# ethernet.net
KiCad netlist of a schematic drawn in Altium Designer
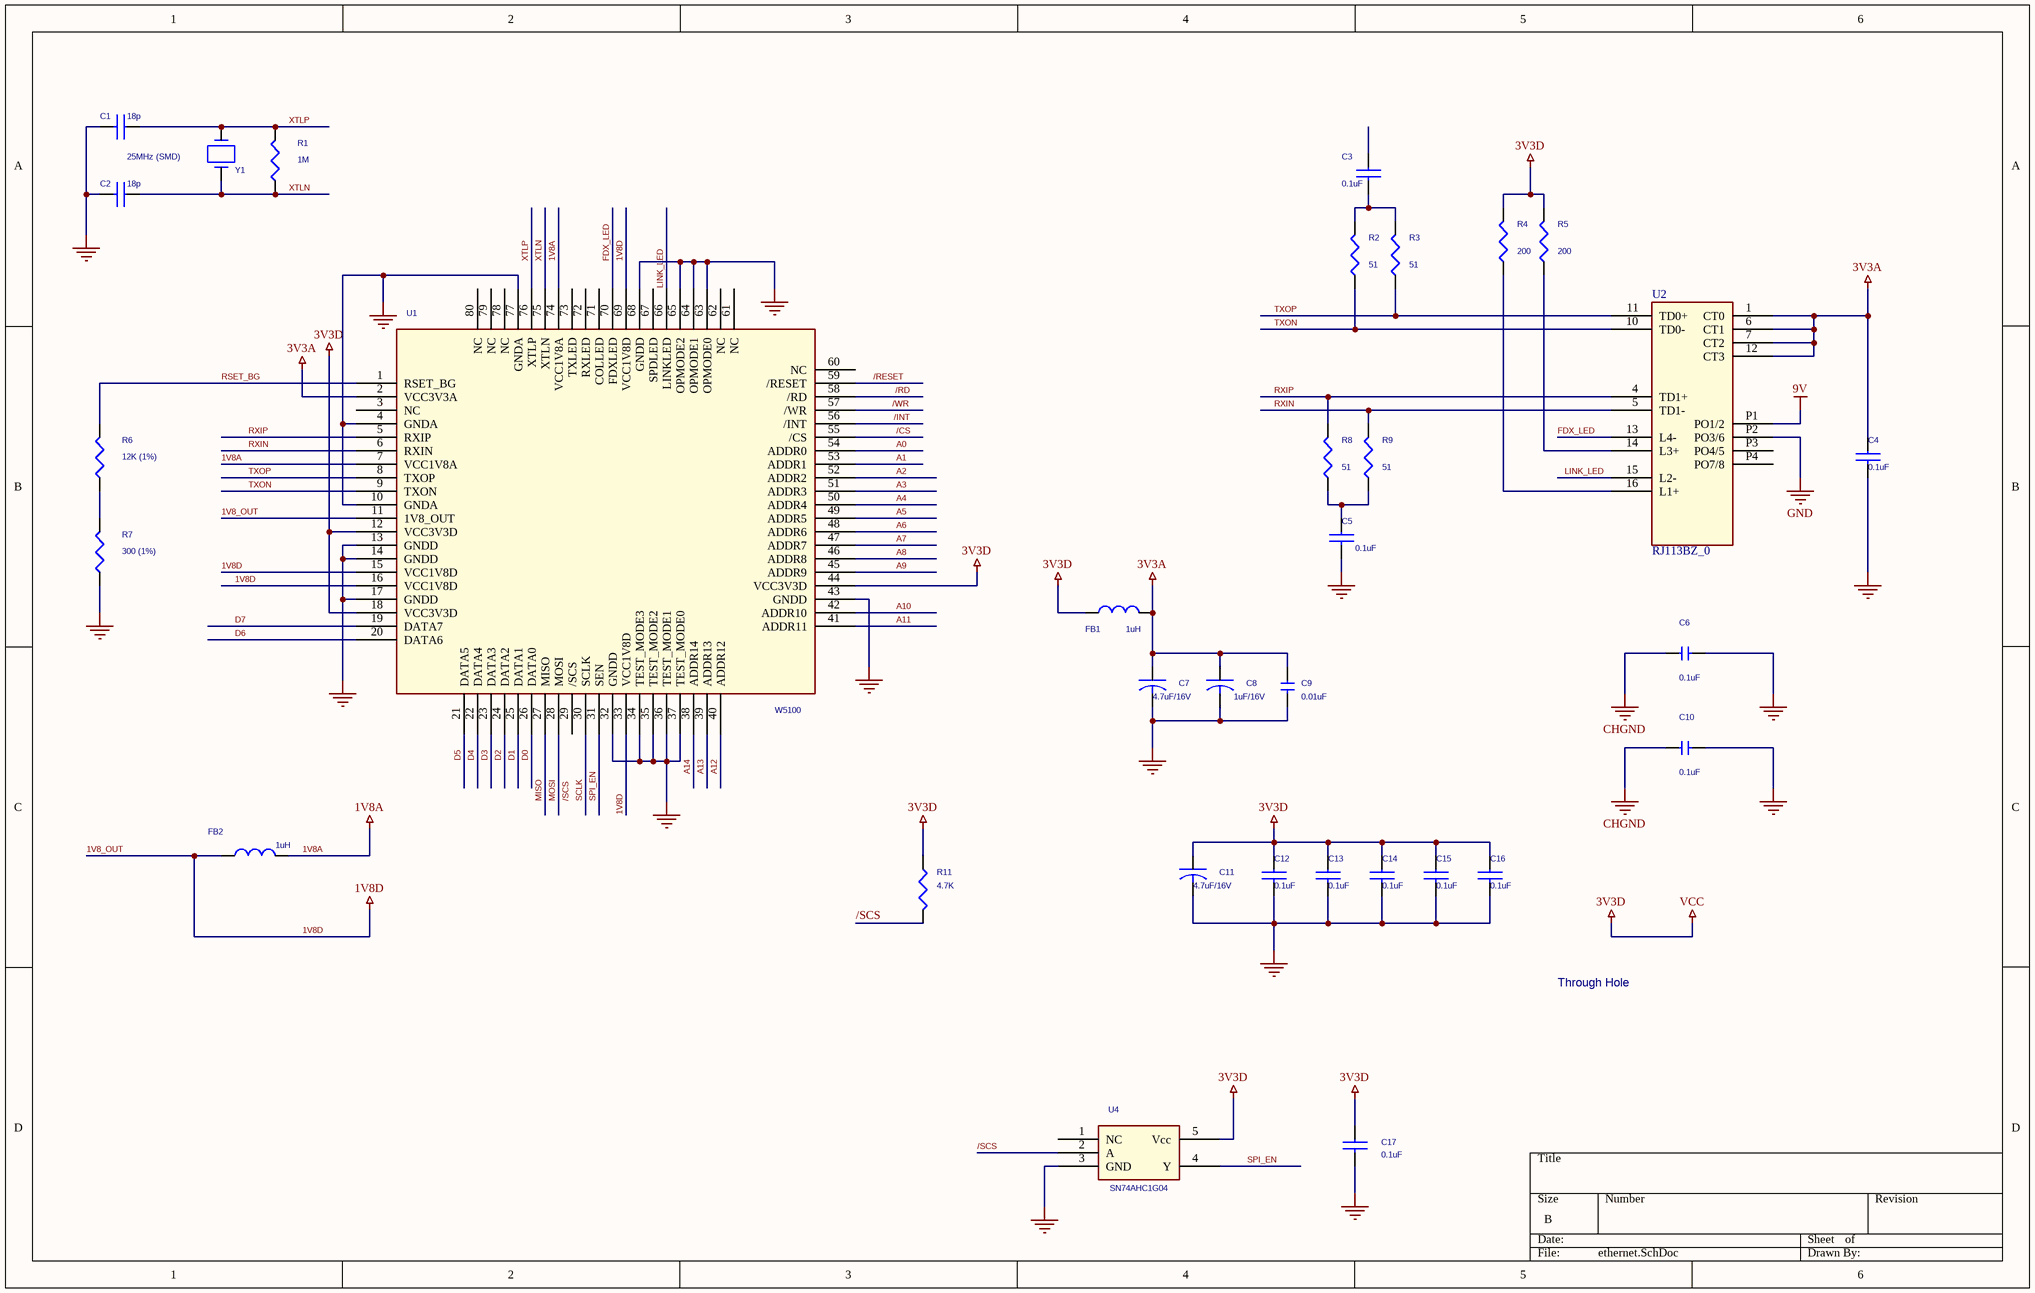
[diagram p0: ethernet.SchDoc]

(export (version "E")
  (design (tool "Eeschema 10.0.6"))
  (components
    (comp (ref "C1") (value "18p") (libsource (lib "*") (part "CAP NP")))
    (comp (ref "C2") (value "18p") (libsource (lib "*") (part "CAP NP")))
    (comp (ref "C3") (value "0.1uF") (libsource (lib "*") (part "CAP NP")))
    (comp (ref "C4") (value "0.1uF") (libsource (lib "*") (part "CAP NP")))
    (comp (ref "C5") (value "0.1uF") (libsource (lib "*") (part "CAP NP")))
    (comp (ref "C6") (value "0.1uF") (footprint "C0603") (libsource (lib "*") (part "CAP_0.01uF_0603")))
    (comp (ref "C7")
      (value "4.7uF/16V")
      (footprint "CAP\\B\\3528")
      (libsource (lib "*") (part "CAP_4.7uF_B"))
    )
    (comp (ref "C8") (value "1uF/16V") (footprint "CAP\\A\\3216") (libsource (lib "*") (part "CAP_1uF_A")))
    (comp (ref "C9") (value "0.01uF") (footprint "C0603") (libsource (lib "*") (part "CAP_0.01uF_0603")))
    (comp (ref "C10") (value "0.1uF") (footprint "C0603") (libsource (lib "*") (part "CAP_0.01uF_0603")))
    (comp (ref "C11")
      (value "4.7uF/16V")
      (footprint "CAP\\B\\3528")
      (libsource (lib "*") (part "CAP_4.7uF_B"))
    )
    (comp (ref "C12") (value "0.1uF") (libsource (lib "*") (part "CAP NP")))
    (comp (ref "C13") (value "0.1uF") (libsource (lib "*") (part "CAP NP")))
    (comp (ref "C14") (value "0.1uF") (libsource (lib "*") (part "CAP NP")))
    (comp (ref "C15") (value "0.1uF") (libsource (lib "*") (part "CAP NP")))
    (comp (ref "C16") (value "0.1uF") (libsource (lib "*") (part "CAP NP")))
    (comp (ref "C17") (value "0.1uF") (libsource (lib "*") (part "CAP NP")))
    (comp (ref "FB1") (value "1uH") (footprint "L0805") (libsource (lib "*") (part "FB_0805")))
    (comp (ref "FB2") (value "1uH") (footprint "L0805") (libsource (lib "*") (part "FB_0805")))
    (comp (ref "R1") (value "1M") (libsource (lib "*") (part "R_Dup1")))
    (comp (ref "R2") (value "51") (libsource (lib "*") (part "R")))
    (comp (ref "R3") (value "51") (libsource (lib "*") (part "R")))
    (comp (ref "R4") (value "200") (libsource (lib "*") (part "R")))
    (comp (ref "R5") (value "200") (libsource (lib "*") (part "R")))
    (comp (ref "R6") (value "12K (1%)") (libsource (lib "*") (part "R_Dup1")))
    (comp (ref "R7") (value "300 (1%)") (libsource (lib "*") (part "R_Dup1")))
    (comp (ref "R8") (value "51") (libsource (lib "*") (part "R")))
    (comp (ref "R9") (value "51") (libsource (lib "*") (part "R")))
    (comp (ref "R11") (value "4.7K") (libsource (lib "*") (part "R")))
    (comp (ref "U1") (value "W5100") (libsource (lib "*") (part "W5100_7")))
    (comp (ref "U2")
      (value "RJ113BZ_0")
      (libsource (lib "WIZ811MJ REV.1.0_RELEASE VER__Library") (part "RJ113BZ_0"))
    )
    (comp (ref "U4") (value "SN74AHC1G04") (libsource (lib "*") (part "SN74AHC1G04")))
    (comp (ref "Y1") (value "25MHz (SMD)") (libsource (lib "*") (part "CRYSTAL")))
  )
  (nets
    (net (code "1") (name "/A0") (class "Default")
      (node (ref "U1") (pin "54") (pinfunction "ADDR0_54") (pintype "passive"))
    )
    (net (code "2") (name "/A1") (class "Default")
      (node (ref "U1") (pin "53") (pinfunction "ADDR1_53") (pintype "passive"))
    )
    (net (code "3") (name "/A2") (class "Default")
      (node (ref "U1") (pin "52") (pinfunction "ADDR2_52") (pintype "passive"))
    )
    (net (code "4") (name "/A3") (class "Default")
      (node (ref "U1") (pin "51") (pinfunction "ADDR3_51") (pintype "passive"))
    )
    (net (code "5") (name "/A4") (class "Default")
      (node (ref "U1") (pin "50") (pinfunction "ADDR4_50") (pintype "passive"))
    )
    (net (code "6") (name "/A5") (class "Default")
      (node (ref "U1") (pin "49") (pinfunction "ADDR5_49") (pintype "passive"))
    )
    (net (code "7") (name "/A6") (class "Default")
      (node (ref "U1") (pin "48") (pinfunction "ADDR6_48") (pintype "passive"))
    )
    (net (code "8") (name "/A7") (class "Default")
      (node (ref "U1") (pin "47") (pinfunction "ADDR7_47") (pintype "passive"))
    )
    (net (code "9") (name "/A8") (class "Default")
      (node (ref "U1") (pin "46") (pinfunction "ADDR8_46") (pintype "passive"))
    )
    (net (code "10") (name "/A9") (class "Default")
      (node (ref "U1") (pin "45") (pinfunction "ADDR9_45") (pintype "passive"))
    )
    (net (code "11") (name "/A10") (class "Default")
      (node (ref "U1") (pin "42") (pinfunction "ADDR10_42") (pintype "passive"))
    )
    (net (code "12") (name "/A11") (class "Default")
      (node (ref "U1") (pin "41") (pinfunction "ADDR11_41") (pintype "passive"))
    )
    (net (code "13") (name "/A12") (class "Default")
      (node (ref "U1") (pin "40") (pinfunction "ADDR12_40") (pintype "passive"))
    )
    (net (code "14") (name "/A13") (class "Default")
      (node (ref "U1") (pin "39") (pinfunction "ADDR13_39") (pintype "passive"))
    )
    (net (code "15") (name "/A14") (class "Default")
      (node (ref "U1") (pin "38") (pinfunction "ADDR14_38") (pintype "passive"))
    )
    (net (code "16") (name "/D0") (class "Default")
      (node (ref "U1") (pin "26") (pinfunction "DATA0_26") (pintype "passive"))
    )
    (net (code "17") (name "/D1") (class "Default")
      (node (ref "U1") (pin "25") (pinfunction "DATA1_25") (pintype "passive"))
    )
    (net (code "18") (name "/D2") (class "Default")
      (node (ref "U1") (pin "24") (pinfunction "DATA2_24") (pintype "passive"))
    )
    (net (code "19") (name "/D3") (class "Default")
      (node (ref "U1") (pin "23") (pinfunction "DATA3_23") (pintype "passive"))
    )
    (net (code "20") (name "/D4") (class "Default")
      (node (ref "U1") (pin "22") (pinfunction "DATA4_22") (pintype "passive"))
    )
    (net (code "21") (name "/D5") (class "Default")
      (node (ref "U1") (pin "21") (pinfunction "DATA5_21") (pintype "passive"))
    )
    (net (code "22") (name "/D6") (class "Default")
      (node (ref "U1") (pin "20") (pinfunction "DATA6_20") (pintype "passive"))
    )
    (net (code "23") (name "/D7") (class "Default")
      (node (ref "U1") (pin "19") (pinfunction "DATA7_19") (pintype "passive"))
    )
    (net (code "24") (name "/FDX_LED") (class "Default")
      (node (ref "U1") (pin "70") (pinfunction "FDXLED_70") (pintype "passive"))
      (node (ref "U2") (pin "13") (pinfunction "L4-_13") (pintype "passive"))
    )
    (net (code "25") (name "/LINK_LED") (class "Default")
      (node (ref "U1") (pin "66") (pinfunction "LINKLED_66") (pintype "passive"))
      (node (ref "U2") (pin "15") (pinfunction "L2-_15") (pintype "passive"))
    )
    (net (code "26") (name "/MISO") (class "Default")
      (node (ref "U1") (pin "27") (pinfunction "MISO_27") (pintype "passive"))
    )
    (net (code "27") (name "/MOSI") (class "Default")
      (node (ref "U1") (pin "28") (pinfunction "MOSI_28") (pintype "passive"))
    )
    (net (code "28") (name "/RSET_BG") (class "Default")
      (node (ref "R6") (pin "2") (pinfunction "2_2") (pintype "passive"))
      (node (ref "U1") (pin "1") (pinfunction "RSET_BG_1") (pintype "passive"))
    )
    (net (code "29") (name "/RXIN") (class "Default")
      (node (ref "R9") (pin "2") (pinfunction "2_2") (pintype "passive"))
      (node (ref "U1") (pin "6") (pinfunction "RXIN_6") (pintype "passive"))
      (node (ref "U2") (pin "5") (pinfunction "TD1-_5") (pintype "passive"))
    )
    (net (code "30") (name "/RXIP") (class "Default")
      (node (ref "R8") (pin "2") (pinfunction "2_2") (pintype "passive"))
      (node (ref "U1") (pin "5") (pinfunction "RXIP_5") (pintype "passive"))
      (node (ref "U2") (pin "4") (pinfunction "TD1+_4") (pintype "passive"))
    )
    (net (code "31") (name "/SCLK") (class "Default")
      (node (ref "U1") (pin "30") (pinfunction "SCLK_30") (pintype "passive"))
    )
    (net (code "32") (name "/SPI_EN") (class "Default")
      (node (ref "U1") (pin "31") (pinfunction "SEN_31") (pintype "passive"))
      (node (ref "U4") (pin "4") (pinfunction "Y_4") (pintype "passive"))
    )
    (net (code "33") (name "/TXON") (class "Default")
      (node (ref "R2") (pin "1") (pinfunction "1_1") (pintype "passive"))
      (node (ref "U1") (pin "9") (pinfunction "TXON_9") (pintype "passive"))
      (node (ref "U2") (pin "10") (pinfunction "TD0-_10") (pintype "passive"))
    )
    (net (code "34") (name "/TXOP") (class "Default")
      (node (ref "R3") (pin "1") (pinfunction "1_1") (pintype "passive"))
      (node (ref "U1") (pin "8") (pinfunction "TXOP_8") (pintype "passive"))
      (node (ref "U2") (pin "11") (pinfunction "TD0+_11") (pintype "passive"))
    )
    (net (code "35") (name "/XTLN") (class "Default")
      (node (ref "C2") (pin "1") (pinfunction "1_1") (pintype "passive"))
      (node (ref "R1") (pin "1") (pinfunction "1_1") (pintype "passive"))
      (node (ref "U1") (pin "75") (pinfunction "XTLN_75") (pintype "passive"))
      (node (ref "Y1") (pin "2") (pinfunction "2_2") (pintype "passive"))
    )
    (net (code "36") (name "/XTLP") (class "Default")
      (node (ref "C1") (pin "1") (pinfunction "1_1") (pintype "passive"))
      (node (ref "R1") (pin "2") (pinfunction "2_2") (pintype "passive"))
      (node (ref "U1") (pin "76") (pinfunction "XTLP_76") (pintype "passive"))
      (node (ref "Y1") (pin "1") (pinfunction "1_1") (pintype "passive"))
    )
    (net (code "37") (name "/{slash}CS") (class "Default")
      (node (ref "U1") (pin "55") (pinfunction "/CS_55") (pintype "passive"))
    )
    (net (code "38") (name "/{slash}INT") (class "Default")
      (node (ref "U1") (pin "56") (pinfunction "/INT_56") (pintype "passive"))
    )
    (net (code "39") (name "/{slash}RD") (class "Default")
      (node (ref "U1") (pin "58") (pinfunction "/RD_58") (pintype "passive"))
    )
    (net (code "40") (name "/{slash}RESET") (class "Default")
      (node (ref "U1") (pin "59") (pinfunction "/RESET_59") (pintype "passive"))
    )
    (net (code "41") (name "/{slash}SCS") (class "Default")
      (node (ref "R11") (pin "2") (pinfunction "2_2") (pintype "passive"))
      (node (ref "U4") (pin "2") (pinfunction "A_2") (pintype "passive"))
    )
    (net (code "42") (name "/{slash}WR") (class "Default")
      (node (ref "U1") (pin "57") (pinfunction "/WR_57") (pintype "passive"))
    )
    (net (code "43") (name "1V8A") (class "Default")
      (node (ref "FB2") (pin "2") (pinfunction "2_2") (pintype "passive"))
      (node (ref "U1") (pin "7") (pinfunction "VCC1V8A_7") (pintype "passive"))
      (node (ref "U1") (pin "74") (pinfunction "VCC1V8A_74") (pintype "passive"))
    )
    (net (code "44") (name "1V8D") (class "Default")
      (node (ref "FB2") (pin "1") (pinfunction "1_1") (pintype "passive"))
      (node (ref "U1") (pin "11") (pinfunction "1V8_OUT_11") (pintype "passive"))
      (node (ref "U1") (pin "15") (pinfunction "VCC1V8D_15") (pintype "passive"))
      (node (ref "U1") (pin "16") (pinfunction "VCC1V8D_16") (pintype "passive"))
      (node (ref "U1") (pin "33") (pinfunction "VCC1V8D_33") (pintype "passive"))
      (node (ref "U1") (pin "69") (pinfunction "VCC1V8D_69") (pintype "passive"))
    )
    (net (code "45") (name "3V3A") (class "Default")
      (node (ref "C4") (pin "1") (pinfunction "1_1") (pintype "passive"))
      (node (ref "C7") (pin "1") (pinfunction "1_1") (pintype "passive"))
      (node (ref "C8") (pin "1") (pinfunction "1_1") (pintype "passive"))
      (node (ref "C9") (pin "1") (pinfunction "1_1") (pintype "passive"))
      (node (ref "FB1") (pin "2") (pinfunction "2_2") (pintype "passive"))
      (node (ref "U1") (pin "2") (pinfunction "VCC3V3A_2") (pintype "passive"))
      (node (ref "U2") (pin "1") (pinfunction "CT0_1") (pintype "passive"))
      (node (ref "U2") (pin "12") (pinfunction "CT3_12") (pintype "passive"))
      (node (ref "U2") (pin "6") (pinfunction "CT1_6") (pintype "passive"))
      (node (ref "U2") (pin "7") (pinfunction "CT2_7") (pintype "passive"))
    )
    (net (code "46") (name "3V3D") (class "Default")
      (node (ref "C11") (pin "1") (pinfunction "1_1") (pintype "passive"))
      (node (ref "C12") (pin "1") (pinfunction "1_1") (pintype "passive"))
      (node (ref "C13") (pin "1") (pinfunction "1_1") (pintype "passive"))
      (node (ref "C14") (pin "1") (pinfunction "1_1") (pintype "passive"))
      (node (ref "C15") (pin "1") (pinfunction "1_1") (pintype "passive"))
      (node (ref "C16") (pin "1") (pinfunction "1_1") (pintype "passive"))
      (node (ref "C17") (pin "1") (pinfunction "1_1") (pintype "passive"))
      (node (ref "FB1") (pin "1") (pinfunction "1_1") (pintype "passive"))
      (node (ref "R11") (pin "1") (pinfunction "1_1") (pintype "passive"))
      (node (ref "R4") (pin "2") (pinfunction "2_2") (pintype "passive"))
      (node (ref "R5") (pin "2") (pinfunction "2_2") (pintype "passive"))
      (node (ref "U1") (pin "12") (pinfunction "VCC3V3D_12") (pintype "passive"))
      (node (ref "U1") (pin "18") (pinfunction "VCC3V3D_18") (pintype "passive"))
      (node (ref "U1") (pin "44") (pinfunction "VCC3V3D_44") (pintype "passive"))
      (node (ref "U4") (pin "5") (pinfunction "Vcc_5") (pintype "passive"))
    )
    (net (code "47") (name "9V") (class "Default")
      (node (ref "U2") (pin "P1") (pinfunction "PO1/2_P1") (pintype "passive"))
    )
    (net (code "48") (name "CHGND") (class "Default")
      (node (ref "C10") (pin "1") (pinfunction "1_1") (pintype "passive"))
      (node (ref "C6") (pin "1") (pinfunction "1_1") (pintype "passive"))
    )
    (net (code "49") (name "GND") (class "Default")
      (node (ref "C1") (pin "2") (pinfunction "2_2") (pintype "passive"))
      (node (ref "C10") (pin "2") (pinfunction "2_2") (pintype "passive"))
      (node (ref "C11") (pin "2") (pinfunction "2_2") (pintype "passive"))
      (node (ref "C12") (pin "2") (pinfunction "2_2") (pintype "passive"))
      (node (ref "C13") (pin "2") (pinfunction "2_2") (pintype "passive"))
      (node (ref "C14") (pin "2") (pinfunction "2_2") (pintype "passive"))
      (node (ref "C15") (pin "2") (pinfunction "2_2") (pintype "passive"))
      (node (ref "C16") (pin "2") (pinfunction "2_2") (pintype "passive"))
      (node (ref "C17") (pin "2") (pinfunction "2_2") (pintype "passive"))
      (node (ref "C2") (pin "2") (pinfunction "2_2") (pintype "passive"))
      (node (ref "C4") (pin "2") (pinfunction "2_2") (pintype "passive"))
      (node (ref "C5") (pin "2") (pinfunction "2_2") (pintype "passive"))
      (node (ref "C6") (pin "2") (pinfunction "2_2") (pintype "passive"))
      (node (ref "C7") (pin "2") (pinfunction "2_2") (pintype "passive"))
      (node (ref "C8") (pin "2") (pinfunction "2_2") (pintype "passive"))
      (node (ref "C9") (pin "2") (pinfunction "2_2") (pintype "passive"))
      (node (ref "R7") (pin "1") (pinfunction "1_1") (pintype "passive"))
      (node (ref "U1") (pin "10") (pinfunction "GNDA_10") (pintype "passive"))
      (node (ref "U1") (pin "13") (pinfunction "GNDD_13") (pintype "passive"))
      (node (ref "U1") (pin "14") (pinfunction "GNDD_14") (pintype "passive"))
      (node (ref "U1") (pin "17") (pinfunction "GNDD_17") (pintype "passive"))
      (node (ref "U1") (pin "32") (pinfunction "GNDD_32") (pintype "passive"))
      (node (ref "U1") (pin "34") (pinfunction "TEST_MODE3_34") (pintype "passive"))
      (node (ref "U1") (pin "35") (pinfunction "TEST_MODE2_35") (pintype "passive"))
      (node (ref "U1") (pin "36") (pinfunction "TEST_MODE1_36") (pintype "passive"))
      (node (ref "U1") (pin "37") (pinfunction "TEST_MODE0_37") (pintype "passive"))
      (node (ref "U1") (pin "4") (pinfunction "GNDA_4") (pintype "passive"))
      (node (ref "U1") (pin "43") (pinfunction "GNDD_43") (pintype "passive"))
      (node (ref "U1") (pin "63") (pinfunction "OPMODE0_63") (pintype "passive"))
      (node (ref "U1") (pin "64") (pinfunction "OPMODE1_64") (pintype "passive"))
      (node (ref "U1") (pin "65") (pinfunction "OPMODE2_65") (pintype "passive"))
      (node (ref "U1") (pin "68") (pinfunction "GNDD_68") (pintype "passive"))
      (node (ref "U1") (pin "77") (pinfunction "GNDA_77") (pintype "passive"))
      (node (ref "U2") (pin "P2") (pinfunction "PO3/6_P2") (pintype "passive"))
      (node (ref "U4") (pin "3") (pinfunction "GND_3") (pintype "passive"))
    )
    (net (code "50") (name "Net-(C3-Pad2)") (class "Default")
      (node (ref "C3") (pin "2") (pinfunction "2_2") (pintype "passive"))
      (node (ref "R2") (pin "2") (pinfunction "2_2") (pintype "passive"))
      (node (ref "R3") (pin "2") (pinfunction "2_2") (pintype "passive"))
    )
    (net (code "51") (name "Net-(C5-Pad1)") (class "Default")
      (node (ref "C5") (pin "1") (pinfunction "1_1") (pintype "passive"))
      (node (ref "R8") (pin "1") (pinfunction "1_1") (pintype "passive"))
      (node (ref "R9") (pin "1") (pinfunction "1_1") (pintype "passive"))
    )
    (net (code "52") (name "Net-(R6-Pad1)") (class "Default")
      (node (ref "R6") (pin "1") (pinfunction "1_1") (pintype "passive"))
      (node (ref "R7") (pin "2") (pinfunction "2_2") (pintype "passive"))
    )
    (net (code "53") (name "Net-(U2-L1+)") (class "Default")
      (node (ref "R4") (pin "1") (pinfunction "1_1") (pintype "passive"))
      (node (ref "U2") (pin "16") (pinfunction "L1+_16") (pintype "passive"))
    )
    (net (code "54") (name "Net-(U2-L3+)") (class "Default")
      (node (ref "R5") (pin "1") (pinfunction "1_1") (pintype "passive"))
      (node (ref "U2") (pin "14") (pinfunction "L3+_14") (pintype "passive"))
    )
    (net (code "55") (name "unconnected-(C3-Pad1)") (class "Default")
      (node (ref "C3") (pin "1") (pinfunction "1_1") (pintype "passive"))
    )
    (net (code "56") (name "unconnected-(U1-COLLED-Pad71)") (class "Default")
      (node (ref "U1") (pin "71") (pinfunction "COLLED_71") (pintype "passive"))
    )
    (net (code "57") (name "unconnected-(U1-NC-Pad3)") (class "Default")
      (node (ref "U1") (pin "3") (pinfunction "NC_3") (pintype "passive"))
    )
    (net (code "58") (name "unconnected-(U1-NC-Pad60)") (class "Default")
      (node (ref "U1") (pin "60") (pinfunction "NC_60") (pintype "passive"))
    )
    (net (code "59") (name "unconnected-(U1-NC-Pad61)") (class "Default")
      (node (ref "U1") (pin "61") (pinfunction "NC_61") (pintype "passive"))
    )
    (net (code "60") (name "unconnected-(U1-NC-Pad62)") (class "Default")
      (node (ref "U1") (pin "62") (pinfunction "NC_62") (pintype "passive"))
    )
    (net (code "61") (name "unconnected-(U1-NC-Pad78)") (class "Default")
      (node (ref "U1") (pin "78") (pinfunction "NC_78") (pintype "passive"))
    )
    (net (code "62") (name "unconnected-(U1-NC-Pad79)") (class "Default")
      (node (ref "U1") (pin "79") (pinfunction "NC_79") (pintype "passive"))
    )
    (net (code "63") (name "unconnected-(U1-NC-Pad80)") (class "Default")
      (node (ref "U1") (pin "80") (pinfunction "NC_80") (pintype "passive"))
    )
    (net (code "64") (name "unconnected-(U1-RXLED-Pad72)") (class "Default")
      (node (ref "U1") (pin "72") (pinfunction "RXLED_72") (pintype "passive"))
    )
    (net (code "65") (name "unconnected-(U1-SPDLED-Pad67)") (class "Default")
      (node (ref "U1") (pin "67") (pinfunction "SPDLED_67") (pintype "passive"))
    )
    (net (code "66") (name "unconnected-(U1-TXLED-Pad73)") (class "Default")
      (node (ref "U1") (pin "73") (pinfunction "TXLED_73") (pintype "passive"))
    )
    (net (code "67") (name "unconnected-(U1-{slash}SCS-Pad29)") (class "Default")
      (node (ref "U1") (pin "29") (pinfunction "/SCS_29") (pintype "passive"))
    )
    (net (code "68") (name "unconnected-(U2-PO4{slash}5-PadP3)") (class "Default")
      (node (ref "U2") (pin "P3") (pinfunction "PO4/5_P3") (pintype "passive"))
    )
    (net (code "69") (name "unconnected-(U2-PO7{slash}8-PadP4)") (class "Default")
      (node (ref "U2") (pin "P4") (pinfunction "PO7/8_P4") (pintype "passive"))
    )
    (net (code "70") (name "unconnected-(U4-NC-Pad1)") (class "Default")
      (node (ref "U4") (pin "1") (pinfunction "NC_1") (pintype "passive"))
    )
  )
)
